# Sunfish_ECU_RevA.net
KiCad netlist of a schematic drawn in Altium Designer
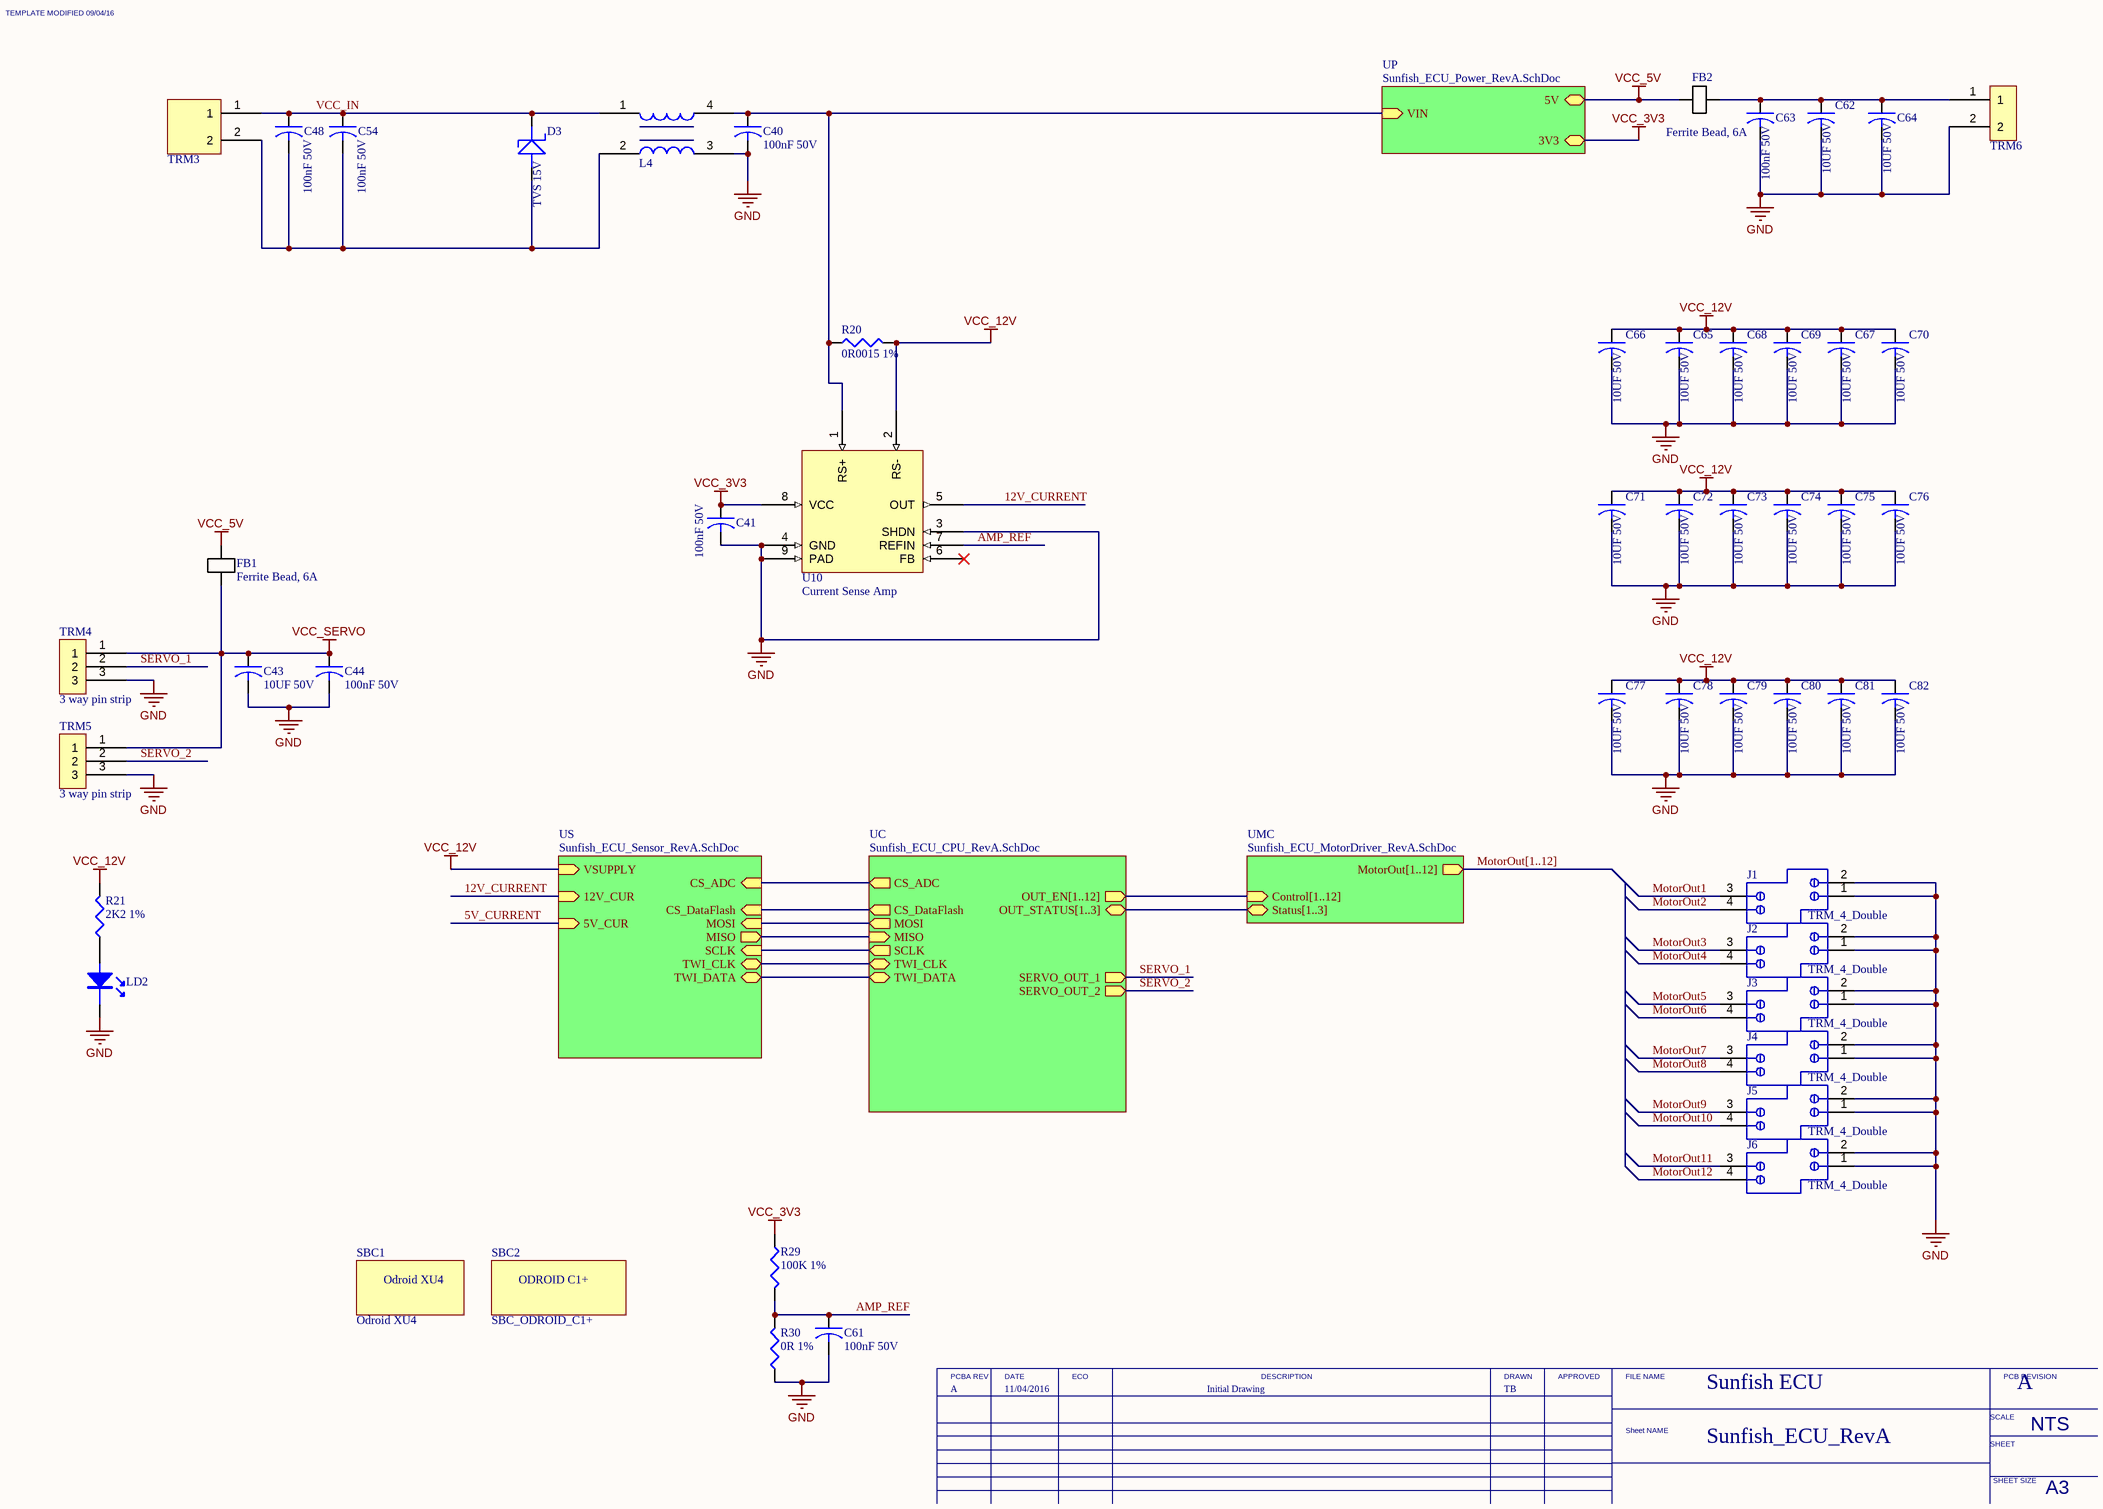
[diagram p0: Sunfish_ECU_RevA.SchDoc]

(export (version "E")
  (design (tool "Eeschema 10.0.6"))
  (components
    (comp (ref "C40")
      (value "100nF 50V")
      (footprint "0603")
      (description "CAP CER 100nF 50V 10% X7R 0603")
      (fields (field (name "MANUFACTURER") "Murata"))
      (libsource (lib "Caps") (part "CAP_100NF_50V_10%_0603"))
    )
    (comp (ref "C41")
      (value "100nF 50V")
      (footprint "0603")
      (description "CAP CER 100nF 50V 10% X7R 0603")
      (fields (field (name "MANUFACTURER") "Murata"))
      (libsource (lib "Caps") (part "CAP_100NF_50V_10%_0603"))
    )
    (comp (ref "C43")
      (value "10UF 50V")
      (footprint "1206")
      (description "CAP CER 10UF 50V 10% X5R 1206")
      (fields (field (name "MANUFACTURER") "Murata"))
      (libsource (lib "Caps") (part "CAP_10UF_50V_10%_1206"))
    )
    (comp (ref "C44")
      (value "100nF 50V")
      (footprint "0603")
      (description "CAP CER 100nF 50V 10% X7R 0603")
      (fields (field (name "MANUFACTURER") "Murata"))
      (libsource (lib "Caps") (part "CAP_100NF_50V_10%_0603"))
    )
    (comp (ref "C48")
      (value "100nF 50V")
      (footprint "0603")
      (description "CAP CER 100nF 50V 10% X7R 0603")
      (fields (field (name "MANUFACTURER") "Murata"))
      (libsource (lib "Caps") (part "CAP_100NF_50V_10%_0603"))
    )
    (comp (ref "C54")
      (value "100nF 50V")
      (footprint "0603")
      (description "CAP CER 100nF 50V 10% X7R 0603")
      (fields (field (name "MANUFACTURER") "Murata"))
      (libsource (lib "Caps") (part "CAP_100NF_50V_10%_0603"))
    )
    (comp (ref "C61")
      (value "100nF 50V")
      (footprint "0603")
      (description "CAP CER 100nF 50V 10% X7R 0603")
      (fields (field (name "MANUFACTURER") "Murata"))
      (libsource (lib "ThrusterControl") (part "CAP_100NF_50V_10%_0603"))
    )
    (comp (ref "C62")
      (value "10UF 50V")
      (footprint "1206")
      (description "CAP CER 10UF 50V 10% X5R 1206")
      (fields (field (name "MANUFACTURER") "Murata"))
      (libsource (lib "ThrusterControl") (part "CAP_10UF_50V_10%_1206"))
    )
    (comp (ref "C63")
      (value "100nF 50V")
      (footprint "0603")
      (description "CAP CER 100nF 50V 10% X7R 0603")
      (fields (field (name "MANUFACTURER") "Murata"))
      (libsource (lib "Caps") (part "CAP_100NF_50V_10%_0603"))
    )
    (comp (ref "C64")
      (value "10UF 50V")
      (footprint "1206")
      (description "CAP CER 10UF 50V 10% X5R 1206")
      (fields (field (name "MANUFACTURER") "Murata"))
      (libsource (lib "ThrusterControl") (part "CAP_10UF_50V_10%_1206"))
    )
    (comp (ref "C65")
      (value "10UF 50V")
      (footprint "1206")
      (description "CAP CER 10UF 50V 10% X5R 1206")
      (fields (field (name "MANUFACTURER") "Murata"))
      (libsource (lib "ThrusterControl") (part "CAP_10UF_50V_10%_1206"))
    )
    (comp (ref "C66")
      (value "10UF 50V")
      (footprint "1206")
      (description "CAP CER 10UF 50V 10% X5R 1206")
      (fields (field (name "MANUFACTURER") "Murata"))
      (libsource (lib "ThrusterControl") (part "CAP_10UF_50V_10%_1206"))
    )
    (comp (ref "C67")
      (value "10UF 50V")
      (footprint "1206")
      (description "CAP CER 10UF 50V 10% X5R 1206")
      (fields (field (name "MANUFACTURER") "Murata"))
      (libsource (lib "ThrusterControl") (part "CAP_10UF_50V_10%_1206"))
    )
    (comp (ref "C68")
      (value "10UF 50V")
      (footprint "1206")
      (description "CAP CER 10UF 50V 10% X5R 1206")
      (fields (field (name "MANUFACTURER") "Murata"))
      (libsource (lib "ThrusterControl") (part "CAP_10UF_50V_10%_1206"))
    )
    (comp (ref "C69")
      (value "10UF 50V")
      (footprint "1206")
      (description "CAP CER 10UF 50V 10% X5R 1206")
      (fields (field (name "MANUFACTURER") "Murata"))
      (libsource (lib "ThrusterControl") (part "CAP_10UF_50V_10%_1206"))
    )
    (comp (ref "C70")
      (value "10UF 50V")
      (footprint "1206")
      (description "CAP CER 10UF 50V 10% X5R 1206")
      (fields (field (name "MANUFACTURER") "Murata"))
      (libsource (lib "ThrusterControl") (part "CAP_10UF_50V_10%_1206"))
    )
    (comp (ref "C71")
      (value "10UF 50V")
      (footprint "1206")
      (description "CAP CER 10UF 50V 10% X5R 1206")
      (fields (field (name "MANUFACTURER") "Murata"))
      (libsource (lib "ThrusterControl") (part "CAP_10UF_50V_10%_1206"))
    )
    (comp (ref "C72")
      (value "10UF 50V")
      (footprint "1206")
      (description "CAP CER 10UF 50V 10% X5R 1206")
      (fields (field (name "MANUFACTURER") "Murata"))
      (libsource (lib "ThrusterControl") (part "CAP_10UF_50V_10%_1206"))
    )
    (comp (ref "C73")
      (value "10UF 50V")
      (footprint "1206")
      (description "CAP CER 10UF 50V 10% X5R 1206")
      (fields (field (name "MANUFACTURER") "Murata"))
      (libsource (lib "ThrusterControl") (part "CAP_10UF_50V_10%_1206"))
    )
    (comp (ref "C74")
      (value "10UF 50V")
      (footprint "1206")
      (description "CAP CER 10UF 50V 10% X5R 1206")
      (fields (field (name "MANUFACTURER") "Murata"))
      (libsource (lib "ThrusterControl") (part "CAP_10UF_50V_10%_1206"))
    )
    (comp (ref "C75")
      (value "10UF 50V")
      (footprint "1206")
      (description "CAP CER 10UF 50V 10% X5R 1206")
      (fields (field (name "MANUFACTURER") "Murata"))
      (libsource (lib "ThrusterControl") (part "CAP_10UF_50V_10%_1206"))
    )
    (comp (ref "C76")
      (value "10UF 50V")
      (footprint "1206")
      (description "CAP CER 10UF 50V 10% X5R 1206")
      (fields (field (name "MANUFACTURER") "Murata"))
      (libsource (lib "ThrusterControl") (part "CAP_10UF_50V_10%_1206"))
    )
    (comp (ref "C77")
      (value "10UF 50V")
      (footprint "1206")
      (description "CAP CER 10UF 50V 10% X5R 1206")
      (fields (field (name "MANUFACTURER") "Murata"))
      (libsource (lib "ThrusterControl") (part "CAP_10UF_50V_10%_1206"))
    )
    (comp (ref "C78")
      (value "10UF 50V")
      (footprint "1206")
      (description "CAP CER 10UF 50V 10% X5R 1206")
      (fields (field (name "MANUFACTURER") "Murata"))
      (libsource (lib "ThrusterControl") (part "CAP_10UF_50V_10%_1206"))
    )
    (comp (ref "C79")
      (value "10UF 50V")
      (footprint "1206")
      (description "CAP CER 10UF 50V 10% X5R 1206")
      (fields (field (name "MANUFACTURER") "Murata"))
      (libsource (lib "ThrusterControl") (part "CAP_10UF_50V_10%_1206"))
    )
    (comp (ref "C80")
      (value "10UF 50V")
      (footprint "1206")
      (description "CAP CER 10UF 50V 10% X5R 1206")
      (fields (field (name "MANUFACTURER") "Murata"))
      (libsource (lib "ThrusterControl") (part "CAP_10UF_50V_10%_1206"))
    )
    (comp (ref "C81")
      (value "10UF 50V")
      (footprint "1206")
      (description "CAP CER 10UF 50V 10% X5R 1206")
      (fields (field (name "MANUFACTURER") "Murata"))
      (libsource (lib "ThrusterControl") (part "CAP_10UF_50V_10%_1206"))
    )
    (comp (ref "C82")
      (value "10UF 50V")
      (footprint "1206")
      (description "CAP CER 10UF 50V 10% X5R 1206")
      (fields (field (name "MANUFACTURER") "Murata"))
      (libsource (lib "ThrusterControl") (part "CAP_10UF_50V_10%_1206"))
    )
    (comp (ref "D3")
      (value "TVS 15V")
      (footprint "DO-214AB")
      (description "TVS Diode, 15V")
      (fields (field (name "MANUFACTURER") "LIttlefuse"))
      (libsource (lib "Semiconductors") (part "DIODE_TVS_SMCJ15A"))
    )
    (comp (ref "FB1")
      (value "Ferrite Bead, 6A")
      (footprint "1806")
      (fields (field (name "MANUFACTURER") "MURATA"))
      (libsource (lib "Inductors") (part "IND_FERRITE_ BLM41PG600SN1L"))
    )
    (comp (ref "FB2")
      (value "Ferrite Bead, 6A")
      (footprint "1806")
      (fields (field (name "MANUFACTURER") "MURATA"))
      (libsource (lib "Inductors") (part "IND_FERRITE_ BLM41PG600SN1L"))
    )
    (comp (ref "J1")
      (value "TRM_4_Double")
      (footprint "691230110004")
      (description "WR-TBL Terminal Blocks Serie 2301 - 3.50 mm with Rising Clamp")
      (fields
        (field (name "MANUFACTURER") "Würth Elektronik eiSos GmbH")
        (field (name "PARTNO") "691230110004")
        (field (name "CREATED DATE") "8 Novenber 2013")
        (field (name "CREATED BY") "Karrer Zheng")
      )
      (libsource (lib "Hardware") (part "TRM_4_Double"))
    )
    (comp (ref "J2")
      (value "TRM_4_Double")
      (footprint "691230110004")
      (description "WR-TBL Terminal Blocks Serie 2301 - 3.50 mm with Rising Clamp")
      (fields
        (field (name "MANUFACTURER") "Würth Elektronik eiSos GmbH")
        (field (name "PARTNO") "691230110004")
        (field (name "CREATED DATE") "8 Novenber 2013")
        (field (name "CREATED BY") "Karrer Zheng")
      )
      (libsource (lib "Hardware") (part "TRM_4_Double"))
    )
    (comp (ref "J3")
      (value "TRM_4_Double")
      (footprint "691230110004")
      (description "WR-TBL Terminal Blocks Serie 2301 - 3.50 mm with Rising Clamp")
      (fields
        (field (name "MANUFACTURER") "Würth Elektronik eiSos GmbH")
        (field (name "PARTNO") "691230110004")
        (field (name "CREATED DATE") "8 Novenber 2013")
        (field (name "CREATED BY") "Karrer Zheng")
      )
      (libsource (lib "Hardware") (part "TRM_4_Double"))
    )
    (comp (ref "J4")
      (value "TRM_4_Double")
      (footprint "691230110004")
      (description "WR-TBL Terminal Blocks Serie 2301 - 3.50 mm with Rising Clamp")
      (fields
        (field (name "MANUFACTURER") "Würth Elektronik eiSos GmbH")
        (field (name "PARTNO") "691230110004")
        (field (name "CREATED DATE") "8 Novenber 2013")
        (field (name "CREATED BY") "Karrer Zheng")
      )
      (libsource (lib "Hardware") (part "TRM_4_Double"))
    )
    (comp (ref "J5")
      (value "TRM_4_Double")
      (footprint "691230110004")
      (description "WR-TBL Terminal Blocks Serie 2301 - 3.50 mm with Rising Clamp")
      (fields
        (field (name "MANUFACTURER") "Würth Elektronik eiSos GmbH")
        (field (name "PARTNO") "691230110004")
        (field (name "CREATED DATE") "8 Novenber 2013")
        (field (name "CREATED BY") "Karrer Zheng")
      )
      (libsource (lib "Hardware") (part "TRM_4_Double"))
    )
    (comp (ref "J6")
      (value "TRM_4_Double")
      (footprint "691230110004")
      (description "WR-TBL Terminal Blocks Serie 2301 - 3.50 mm with Rising Clamp")
      (fields
        (field (name "MANUFACTURER") "Würth Elektronik eiSos GmbH")
        (field (name "PARTNO") "691230110004")
        (field (name "CREATED DATE") "8 Novenber 2013")
        (field (name "CREATED BY") "Karrer Zheng")
      )
      (libsource (lib "Hardware") (part "TRM_4_Double"))
    )
    (comp (ref "L4")
      (value "CHOKE COM MODE ULTRA HC 100 OHMS")
      (footprint "Choke_CM5441Z101B-10")
      (fields (field (name "MANUFACTURER") "Laird-Signal Integrity Products"))
      (libsource (lib "Inductors") (part "CHOKE_COM_MODE_100MHz"))
    )
    (comp (ref "LD2")
      (value "Green LED 0805")
      (footprint "0805DIODE")
      (description "WL-SMCW SMD CHIP LED WATERCLEAR")
      (fields (field (name "MANUFACTURER") "Wurth"))
      (libsource (lib "Semiconductors") (part "LED_Green_0805"))
    )
    (comp (ref "R20")
      (value "0R0015 1%")
      (footprint "2512")
      (description "Resistor, 0R0015, 1%, 2512")
      (fields (field (name "MANUFACTURER") "Riedon"))
      (libsource (lib "Resistors") (part "RES_0R0015_1%_2512"))
    )
    (comp (ref "R21")
      (value "2K2 1%")
      (footprint "0603")
      (description "Resistor, 2K2, 1%, 0603")
      (fields (field (name "MANUFACTURER") "Bourns Inc"))
      (libsource (lib "Resistors") (part "RES_2K2_1%_0603"))
    )
    (comp (ref "R29")
      (value "100K 1%")
      (footprint "0603")
      (description "Resistor, 100K, 1%, 0603")
      (fields (field (name "MANUFACTURER") "Bourns Inc"))
      (libsource (lib "ThrusterControl") (part "RES_100K_1%_0603"))
    )
    (comp (ref "R30")
      (value "0R 1%")
      (footprint "0603")
      (description "Resistor, 0R, 1%, 0603")
      (fields (field (name "MANUFACTURER") "Bourns Inc"))
      (libsource (lib "Resistors") (part "RES_0R_1%_0603_1"))
    )
    (comp (ref "SBC1")
      (value "Odroid XU4")
      (footprint "ODROID_XU4")
      (libsource (lib "Hardware") (part "SBC_ODROID_XU4"))
    )
    (comp (ref "SBC2")
      (value "SBC_ODROID_C1+")
      (footprint "SBC_ODROID_C1+")
      (libsource (lib "Hardware") (part "SBC_ODROID_C1+"))
    )
    (comp (ref "TRM3")
      (value "2way screw terminal, High current")
      (footprint "TERM_2POS_HORIZ_7.62MM")
      (description "TERM BLOCK 2POS HORIZ 7.62MM T/H")
      (fields (field (name "MANUFACTURER") "Altronics"))
      (libsource (lib "Hardware") (part "TRM_2way_ScrewTerminal_7.62mm"))
    )
    (comp (ref "TRM4")
      (value "3 way pin strip")
      (footprint "SIP_3")
      (description "3 Way pin strip")
      (libsource (lib "Hardware") (part "TRM_3WaySocket"))
    )
    (comp (ref "TRM5")
      (value "3 way pin strip")
      (footprint "SIP_3")
      (description "3 Way pin strip")
      (libsource (lib "Hardware") (part "TRM_3WaySocket"))
    )
    (comp (ref "TRM6")
      (value "Wurth 2way screw terminal")
      (footprint "TERM_2POS_HORIZ_5.08MM")
      (description "TERM BLOCK 2POS HORIZ 5.08MM T/H")
      (fields (field (name "MANUFACTURER") "Wurth Electronics Inc"))
      (libsource (lib "Hardware") (part "TRM_2way_ScrewTerminal"))
    )
    (comp (ref "U10")
      (value "Current Sense Amp")
      (footprint "SOIC127P600X168_HS-8M")
      (description "IC OPAMP CURR SENSE 230KHZ 8SOIC")
      (fields (field (name "MANUFACTURER") "Maxim Intergrated"))
      (libsource (lib "IC") (part "IC_OPAMP_MAX9920+"))
    )
  )
  (nets
    (net (code "2") (name "/12V_CURRENT") (class "Default")
      (node (ref "U10") (pin "5") (pinfunction "OUT_5") (pintype "output"))
    )
    (net (code "3") (name "/AMP_REF") (class "Default")
      (node (ref "C61") (pin "1") (pinfunction "1_1") (pintype "passive"))
      (node (ref "R29") (pin "1") (pintype "passive"))
      (node (ref "R30") (pin "2") (pintype "passive"))
      (node (ref "U10") (pin "7") (pinfunction "REFIN_7") (pintype "input"))
    )
    (net (code "8") (name "/MotorOut1") (class "Default")
      (node (ref "J1") (pin "3") (pinfunction "3_3") (pintype "passive"))
    )
    (net (code "9") (name "/MotorOut2") (class "Default")
      (node (ref "J1") (pin "4") (pinfunction "4_4") (pintype "passive"))
    )
    (net (code "10") (name "/MotorOut3") (class "Default")
      (node (ref "J2") (pin "3") (pinfunction "3_3") (pintype "passive"))
    )
    (net (code "11") (name "/MotorOut4") (class "Default")
      (node (ref "J2") (pin "4") (pinfunction "4_4") (pintype "passive"))
    )
    (net (code "12") (name "/MotorOut5") (class "Default")
      (node (ref "J3") (pin "3") (pinfunction "3_3") (pintype "passive"))
    )
    (net (code "13") (name "/MotorOut6") (class "Default")
      (node (ref "J3") (pin "4") (pinfunction "4_4") (pintype "passive"))
    )
    (net (code "14") (name "/MotorOut7") (class "Default")
      (node (ref "J4") (pin "3") (pinfunction "3_3") (pintype "passive"))
    )
    (net (code "15") (name "/MotorOut8") (class "Default")
      (node (ref "J4") (pin "4") (pinfunction "4_4") (pintype "passive"))
    )
    (net (code "16") (name "/MotorOut9") (class "Default")
      (node (ref "J5") (pin "3") (pinfunction "3_3") (pintype "passive"))
    )
    (net (code "17") (name "/MotorOut10") (class "Default")
      (node (ref "J5") (pin "4") (pinfunction "4_4") (pintype "passive"))
    )
    (net (code "18") (name "/MotorOut11") (class "Default")
      (node (ref "J6") (pin "3") (pinfunction "3_3") (pintype "passive"))
    )
    (net (code "19") (name "/MotorOut12") (class "Default")
      (node (ref "J6") (pin "4") (pinfunction "4_4") (pintype "passive"))
    )
    (net (code "24") (name "/SERVO_1") (class "Default")
      (node (ref "TRM4") (pin "2") (pinfunction "2_2") (pintype "tri_state"))
    )
    (net (code "25") (name "/SERVO_2") (class "Default")
      (node (ref "TRM5") (pin "2") (pinfunction "2_2") (pintype "tri_state"))
    )
    (net (code "28") (name "/VCC_IN") (class "Default")
      (node (ref "C48") (pin "1") (pinfunction "1_1") (pintype "passive"))
      (node (ref "C54") (pin "1") (pinfunction "1_1") (pintype "passive"))
      (node (ref "D3") (pin "K") (pinfunction "K_K") (pintype "passive"))
      (node (ref "L4") (pin "1") (pinfunction "1_1") (pintype "power_in"))
      (node (ref "TRM3") (pin "1") (pinfunction "1_1") (pintype "tri_state"))
    )
    (net (code "29") (name "/VIN") (class "Default")
      (node (ref "C40") (pin "1") (pinfunction "1_1") (pintype "passive"))
      (node (ref "L4") (pin "4") (pinfunction "4_4") (pintype "power_in"))
      (node (ref "R20") (pin "1") (pintype "passive"))
      (node (ref "U10") (pin "1") (pinfunction "RS+_1") (pintype "input"))
    )
    (net (code "30") (name "GND") (class "Default")
      (node (ref "C40") (pin "2") (pinfunction "2_2") (pintype "passive"))
      (node (ref "C41") (pin "2") (pinfunction "2_2") (pintype "passive"))
      (node (ref "C43") (pin "2") (pinfunction "2_2") (pintype "passive"))
      (node (ref "C44") (pin "2") (pinfunction "2_2") (pintype "passive"))
      (node (ref "C61") (pin "2") (pinfunction "2_2") (pintype "passive"))
      (node (ref "C62") (pin "2") (pinfunction "2_2") (pintype "passive"))
      (node (ref "C63") (pin "2") (pinfunction "2_2") (pintype "passive"))
      (node (ref "C64") (pin "2") (pinfunction "2_2") (pintype "passive"))
      (node (ref "C65") (pin "2") (pinfunction "2_2") (pintype "passive"))
      (node (ref "C66") (pin "2") (pinfunction "2_2") (pintype "passive"))
      (node (ref "C67") (pin "2") (pinfunction "2_2") (pintype "passive"))
      (node (ref "C68") (pin "2") (pinfunction "2_2") (pintype "passive"))
      (node (ref "C69") (pin "2") (pinfunction "2_2") (pintype "passive"))
      (node (ref "C70") (pin "2") (pinfunction "2_2") (pintype "passive"))
      (node (ref "C71") (pin "2") (pinfunction "2_2") (pintype "passive"))
      (node (ref "C72") (pin "2") (pinfunction "2_2") (pintype "passive"))
      (node (ref "C73") (pin "2") (pinfunction "2_2") (pintype "passive"))
      (node (ref "C74") (pin "2") (pinfunction "2_2") (pintype "passive"))
      (node (ref "C75") (pin "2") (pinfunction "2_2") (pintype "passive"))
      (node (ref "C76") (pin "2") (pinfunction "2_2") (pintype "passive"))
      (node (ref "C77") (pin "2") (pinfunction "2_2") (pintype "passive"))
      (node (ref "C78") (pin "2") (pinfunction "2_2") (pintype "passive"))
      (node (ref "C79") (pin "2") (pinfunction "2_2") (pintype "passive"))
      (node (ref "C80") (pin "2") (pinfunction "2_2") (pintype "passive"))
      (node (ref "C81") (pin "2") (pinfunction "2_2") (pintype "passive"))
      (node (ref "C82") (pin "2") (pinfunction "2_2") (pintype "passive"))
      (node (ref "J1") (pin "1") (pinfunction "1_1") (pintype "passive"))
      (node (ref "J1") (pin "2") (pinfunction "2_2") (pintype "passive"))
      (node (ref "J2") (pin "1") (pinfunction "1_1") (pintype "passive"))
      (node (ref "J2") (pin "2") (pinfunction "2_2") (pintype "passive"))
      (node (ref "J3") (pin "1") (pinfunction "1_1") (pintype "passive"))
      (node (ref "J3") (pin "2") (pinfunction "2_2") (pintype "passive"))
      (node (ref "J4") (pin "1") (pinfunction "1_1") (pintype "passive"))
      (node (ref "J4") (pin "2") (pinfunction "2_2") (pintype "passive"))
      (node (ref "J5") (pin "1") (pinfunction "1_1") (pintype "passive"))
      (node (ref "J5") (pin "2") (pinfunction "2_2") (pintype "passive"))
      (node (ref "J6") (pin "1") (pinfunction "1_1") (pintype "passive"))
      (node (ref "J6") (pin "2") (pinfunction "2_2") (pintype "passive"))
      (node (ref "L4") (pin "3") (pinfunction "3_3") (pintype "power_in"))
      (node (ref "LD2") (pin "K") (pintype "passive"))
      (node (ref "R30") (pin "1") (pintype "passive"))
      (node (ref "TRM4") (pin "3") (pinfunction "3_3") (pintype "tri_state"))
      (node (ref "TRM5") (pin "3") (pinfunction "3_3") (pintype "tri_state"))
      (node (ref "TRM6") (pin "2") (pinfunction "2_2") (pintype "tri_state"))
      (node (ref "U10") (pin "3") (pinfunction "SHDN_3") (pintype "input"))
      (node (ref "U10") (pin "4") (pinfunction "GND_4") (pintype "input"))
      (node (ref "U10") (pin "9") (pinfunction "PAD_9") (pintype "input"))
    )
    (net (code "31") (name "Net-(C48-Pad2)") (class "Default")
      (node (ref "C48") (pin "2") (pinfunction "2_2") (pintype "passive"))
      (node (ref "C54") (pin "2") (pinfunction "2_2") (pintype "passive"))
      (node (ref "D3") (pin "A") (pinfunction "A_A") (pintype "passive"))
      (node (ref "L4") (pin "2") (pinfunction "2_2") (pintype "power_in"))
      (node (ref "TRM3") (pin "2") (pinfunction "2_2") (pintype "tri_state"))
    )
    (net (code "32") (name "Net-(C62-Pad1)") (class "Default")
      (node (ref "C62") (pin "1") (pinfunction "1_1") (pintype "passive"))
      (node (ref "C63") (pin "1") (pinfunction "1_1") (pintype "passive"))
      (node (ref "C64") (pin "1") (pinfunction "1_1") (pintype "passive"))
      (node (ref "FB2") (pin "2") (pinfunction "2_2") (pintype "passive"))
      (node (ref "TRM6") (pin "1") (pinfunction "1_1") (pintype "tri_state"))
    )
    (net (code "33") (name "Net-(LD2-PadA)") (class "Default")
      (node (ref "LD2") (pin "A") (pintype "passive"))
      (node (ref "R21") (pin "1") (pintype "passive"))
    )
    (net (code "34") (name "VCC_3V3") (class "Default")
      (node (ref "C41") (pin "1") (pinfunction "1_1") (pintype "passive"))
      (node (ref "R29") (pin "2") (pintype "passive"))
      (node (ref "U10") (pin "8") (pinfunction "VCC_8") (pintype "input"))
    )
    (net (code "35") (name "VCC_5V") (class "Default")
      (node (ref "FB1") (pin "1") (pinfunction "1_1") (pintype "passive"))
      (node (ref "FB2") (pin "1") (pinfunction "1_1") (pintype "passive"))
    )
    (net (code "36") (name "VCC_12V") (class "Default")
      (node (ref "C65") (pin "1") (pinfunction "1_1") (pintype "passive"))
      (node (ref "C66") (pin "1") (pinfunction "1_1") (pintype "passive"))
      (node (ref "C67") (pin "1") (pinfunction "1_1") (pintype "passive"))
      (node (ref "C68") (pin "1") (pinfunction "1_1") (pintype "passive"))
      (node (ref "C69") (pin "1") (pinfunction "1_1") (pintype "passive"))
      (node (ref "C70") (pin "1") (pinfunction "1_1") (pintype "passive"))
      (node (ref "C71") (pin "1") (pinfunction "1_1") (pintype "passive"))
      (node (ref "C72") (pin "1") (pinfunction "1_1") (pintype "passive"))
      (node (ref "C73") (pin "1") (pinfunction "1_1") (pintype "passive"))
      (node (ref "C74") (pin "1") (pinfunction "1_1") (pintype "passive"))
      (node (ref "C75") (pin "1") (pinfunction "1_1") (pintype "passive"))
      (node (ref "C76") (pin "1") (pinfunction "1_1") (pintype "passive"))
      (node (ref "C77") (pin "1") (pinfunction "1_1") (pintype "passive"))
      (node (ref "C78") (pin "1") (pinfunction "1_1") (pintype "passive"))
      (node (ref "C79") (pin "1") (pinfunction "1_1") (pintype "passive"))
      (node (ref "C80") (pin "1") (pinfunction "1_1") (pintype "passive"))
      (node (ref "C81") (pin "1") (pinfunction "1_1") (pintype "passive"))
      (node (ref "C82") (pin "1") (pinfunction "1_1") (pintype "passive"))
      (node (ref "R20") (pin "2") (pintype "passive"))
      (node (ref "R21") (pin "2") (pintype "passive"))
      (node (ref "U10") (pin "2") (pinfunction "RS-_2") (pintype "input"))
    )
    (net (code "37") (name "VCC_SERVO") (class "Default")
      (node (ref "C43") (pin "1") (pinfunction "1_1") (pintype "passive"))
      (node (ref "C44") (pin "1") (pinfunction "1_1") (pintype "passive"))
      (node (ref "FB1") (pin "2") (pinfunction "2_2") (pintype "passive"))
      (node (ref "TRM4") (pin "1") (pinfunction "1_1") (pintype "tri_state"))
      (node (ref "TRM5") (pin "1") (pinfunction "1_1") (pintype "tri_state"))
    )
    (net (code "38") (name "unconnected-(U10-FB-Pad6)") (class "Default")
      (node (ref "U10") (pin "6") (pinfunction "FB_6") (pintype "input+no_connect"))
    )
  )
)
